# ARboard.net
KiCad netlist of a schematic drawn in EAGLE
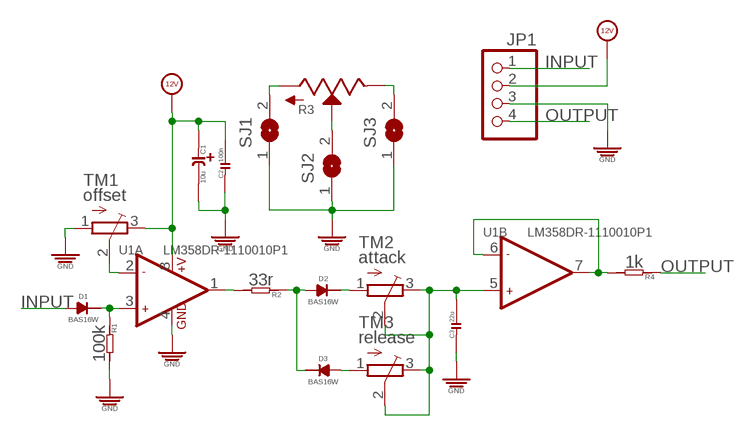
[diagram p0: schematic, sheet 1]

(export (version "E")
  (design (tool "Eeschema 10.0.6"))
  (components
    (comp (ref "C1")
      (value "10u")
      (footprint "eagle-import:CASE-A_3216")
      (libsource (lib "eagle-import") (part "C-POLAR-A"))
    )
    (comp (ref "C2")
      (value "100n")
      (footprint "eagle-import:C0603")
      (libsource (lib "eagle-import") (part "C-0603"))
    )
    (comp (ref "C3")
      (value "22u")
      (footprint "eagle-import:C0603")
      (libsource (lib "eagle-import") (part "C-0603"))
    )
    (comp (ref "D1")
      (value "BAS16W")
      (footprint "eagle-import:SOT-323")
      (libsource (lib "eagle-import") (part "BAS16W"))
    )
    (comp (ref "D2")
      (value "BAS16W")
      (footprint "eagle-import:SOT-323")
      (libsource (lib "eagle-import") (part "BAS16W"))
    )
    (comp (ref "D3")
      (value "BAS16W")
      (footprint "eagle-import:SOT-323")
      (libsource (lib "eagle-import") (part "BAS16W"))
    )
    (comp (ref "JP1")
      (value "PINHD-1X4")
      (footprint "eagle-import:1X04")
      (libsource (lib "eagle-import") (part "PINHD-1X4"))
    )
    (comp (ref "R1")
      (value "100k")
      (footprint "eagle-import:R0603")
      (libsource (lib "eagle-import") (part "R-0603"))
    )
    (comp (ref "R2")
      (value "33r")
      (footprint "eagle-import:R0603")
      (libsource (lib "eagle-import") (part "R-0603"))
    )
    (comp (ref "R3")
      (value "POTSQUAREHOLE_SMALLKNOB")
      (footprint "eagle-import:ALPS_POT_SQUAREHOLES")
      (libsource (lib "eagle-import") (part "POTSQUAREHOLE_SMALLKNOB"))
    )
    (comp (ref "R4")
      (value "1k")
      (footprint "eagle-import:R0603")
      (libsource (lib "eagle-import") (part "R-0603"))
    )
    (comp (ref "SJ1") (value "SJ") (footprint "eagle-import:SJ") (libsource (lib "eagle-import") (part "SJ")))
    (comp (ref "SJ2") (value "SJ") (footprint "eagle-import:SJ") (libsource (lib "eagle-import") (part "SJ")))
    (comp (ref "SJ3") (value "SJ") (footprint "eagle-import:SJ") (libsource (lib "eagle-import") (part "SJ")))
    (comp (ref "TM1")
      (value "offset")
      (footprint "eagle-import:TC33X")
      (libsource (lib "eagle-import") (part "TRIMPOTTC33X"))
    )
    (comp (ref "TM2")
      (value "attack")
      (footprint "eagle-import:TC33X")
      (libsource (lib "eagle-import") (part "TRIMPOTTC33X"))
    )
    (comp (ref "TM3")
      (value "release")
      (footprint "eagle-import:TC33X")
      (libsource (lib "eagle-import") (part "TRIMPOTTC33X"))
    )
    (comp (ref "U1")
      (value "LM358DR-1110010P1")
      (footprint "eagle-import:SOIC8")
      (libsource (lib "eagle-import") (part "LM358DR-1110010P1"))
    )
  )
  (nets
    (net (code "1") (name "/INPUT") (class "Default")
      (node (ref "D1") (pin "ANODE") (pinfunction "ANODE_ANODE") (pintype "bidirectional"))
      (node (ref "JP1") (pin "1") (pinfunction "1_1") (pintype "passive"))
    )
    (net (code "2") (name "/OUTPUT") (class "Default")
      (node (ref "JP1") (pin "4") (pinfunction "4_4") (pintype "passive"))
      (node (ref "R4") (pin "1") (pinfunction "1_1") (pintype "bidirectional"))
    )
    (net (code "3") (name "12V") (class "Default")
      (node (ref "C1") (pin "+") (pinfunction "1_+") (pintype "bidirectional"))
      (node (ref "C2") (pin "2") (pinfunction "2_2") (pintype "bidirectional"))
      (node (ref "JP1") (pin "2") (pinfunction "2_2") (pintype "passive"))
      (node (ref "TM1") (pin "3") (pinfunction "E_3") (pintype "passive"))
      (node (ref "U1") (pin "8") (pinfunction "+V_8") (pintype "power_in"))
    )
    (net (code "4") (name "GND") (class "Default")
      (node (ref "C1") (pin "-") (pinfunction "2_-") (pintype "bidirectional"))
      (node (ref "C2") (pin "1") (pinfunction "1_1") (pintype "bidirectional"))
      (node (ref "C3") (pin "1") (pinfunction "1_1") (pintype "bidirectional"))
      (node (ref "JP1") (pin "3") (pinfunction "3_3") (pintype "passive"))
      (node (ref "R1") (pin "2") (pinfunction "2_2") (pintype "bidirectional"))
      (node (ref "SJ1") (pin "1") (pinfunction "1_1") (pintype "passive"))
      (node (ref "SJ2") (pin "1") (pinfunction "1_1") (pintype "passive"))
      (node (ref "SJ3") (pin "1") (pinfunction "1_1") (pintype "passive"))
      (node (ref "TM1") (pin "1") (pinfunction "A_1") (pintype "passive"))
      (node (ref "U1") (pin "4") (pinfunction "GND_4") (pintype "power_in"))
    )
    (net (code "5") (name "Net-(D2-PadANODE)") (class "Default")
      (node (ref "D2") (pin "ANODE") (pinfunction "ANODE_ANODE") (pintype "bidirectional"))
      (node (ref "D3") (pin "CATHODE") (pinfunction "CATHODE_CATHODE") (pintype "bidirectional"))
      (node (ref "R2") (pin "1") (pinfunction "1_1") (pintype "bidirectional"))
    )
    (net (code "6") (name "Net-(R3-A)") (class "Default")
      (node (ref "R3") (pin "P$3") (pinfunction "A_P$3") (pintype "passive"))
      (node (ref "SJ1") (pin "2") (pinfunction "2_2") (pintype "passive"))
    )
    (net (code "7") (name "Net-(R3-E)") (class "Default")
      (node (ref "R3") (pin "P$1") (pinfunction "E_P$1") (pintype "passive"))
      (node (ref "SJ3") (pin "2") (pinfunction "2_2") (pintype "passive"))
    )
    (net (code "8") (name "Net-(R3-S)") (class "Default")
      (node (ref "R3") (pin "P$2") (pinfunction "S_P$2") (pintype "passive"))
      (node (ref "SJ2") (pin "2") (pinfunction "2_2") (pintype "passive"))
    )
    (net (code "9") (name "Net-(TM1-S)") (class "Default")
      (node (ref "TM1") (pin "2") (pinfunction "S_2") (pintype "passive"))
      (node (ref "U1") (pin "2") (pinfunction "-IN1_2") (pintype "input"))
    )
    (net (code "10") (name "Net-(TM2-A)") (class "Default")
      (node (ref "D2") (pin "CATHODE") (pinfunction "CATHODE_CATHODE") (pintype "bidirectional"))
      (node (ref "TM2") (pin "1") (pinfunction "A_1") (pintype "passive"))
    )
    (net (code "11") (name "Net-(TM2-E)") (class "Default")
      (node (ref "C3") (pin "2") (pinfunction "2_2") (pintype "bidirectional"))
      (node (ref "TM2") (pin "2") (pinfunction "S_2") (pintype "passive"))
      (node (ref "TM2") (pin "3") (pinfunction "E_3") (pintype "passive"))
      (node (ref "TM3") (pin "2") (pinfunction "S_2") (pintype "passive"))
      (node (ref "TM3") (pin "3") (pinfunction "E_3") (pintype "passive"))
      (node (ref "U1") (pin "5") (pinfunction "+IN2_5") (pintype "input"))
    )
    (net (code "12") (name "Net-(TM3-A)") (class "Default")
      (node (ref "D3") (pin "ANODE") (pinfunction "ANODE_ANODE") (pintype "bidirectional"))
      (node (ref "TM3") (pin "1") (pinfunction "A_1") (pintype "passive"))
    )
    (net (code "13") (name "Net-(U1A-+IN1)") (class "Default")
      (node (ref "D1") (pin "CATHODE") (pinfunction "CATHODE_CATHODE") (pintype "bidirectional"))
      (node (ref "R1") (pin "1") (pinfunction "1_1") (pintype "bidirectional"))
      (node (ref "U1") (pin "3") (pinfunction "+IN1_3") (pintype "input"))
    )
    (net (code "14") (name "Net-(U1A-OUT1)") (class "Default")
      (node (ref "R2") (pin "2") (pinfunction "2_2") (pintype "bidirectional"))
      (node (ref "U1") (pin "1") (pinfunction "OUT1_1") (pintype "output"))
    )
    (net (code "15") (name "Net-(U1B--IN2)") (class "Default")
      (node (ref "R4") (pin "2") (pinfunction "2_2") (pintype "bidirectional"))
      (node (ref "U1") (pin "6") (pinfunction "-IN2_6") (pintype "input"))
      (node (ref "U1") (pin "7") (pinfunction "OUT2_7") (pintype "output"))
    )
  )
)
